# I2C_sensors.net
KiCad netlist of a schematic drawn in Altium Designer
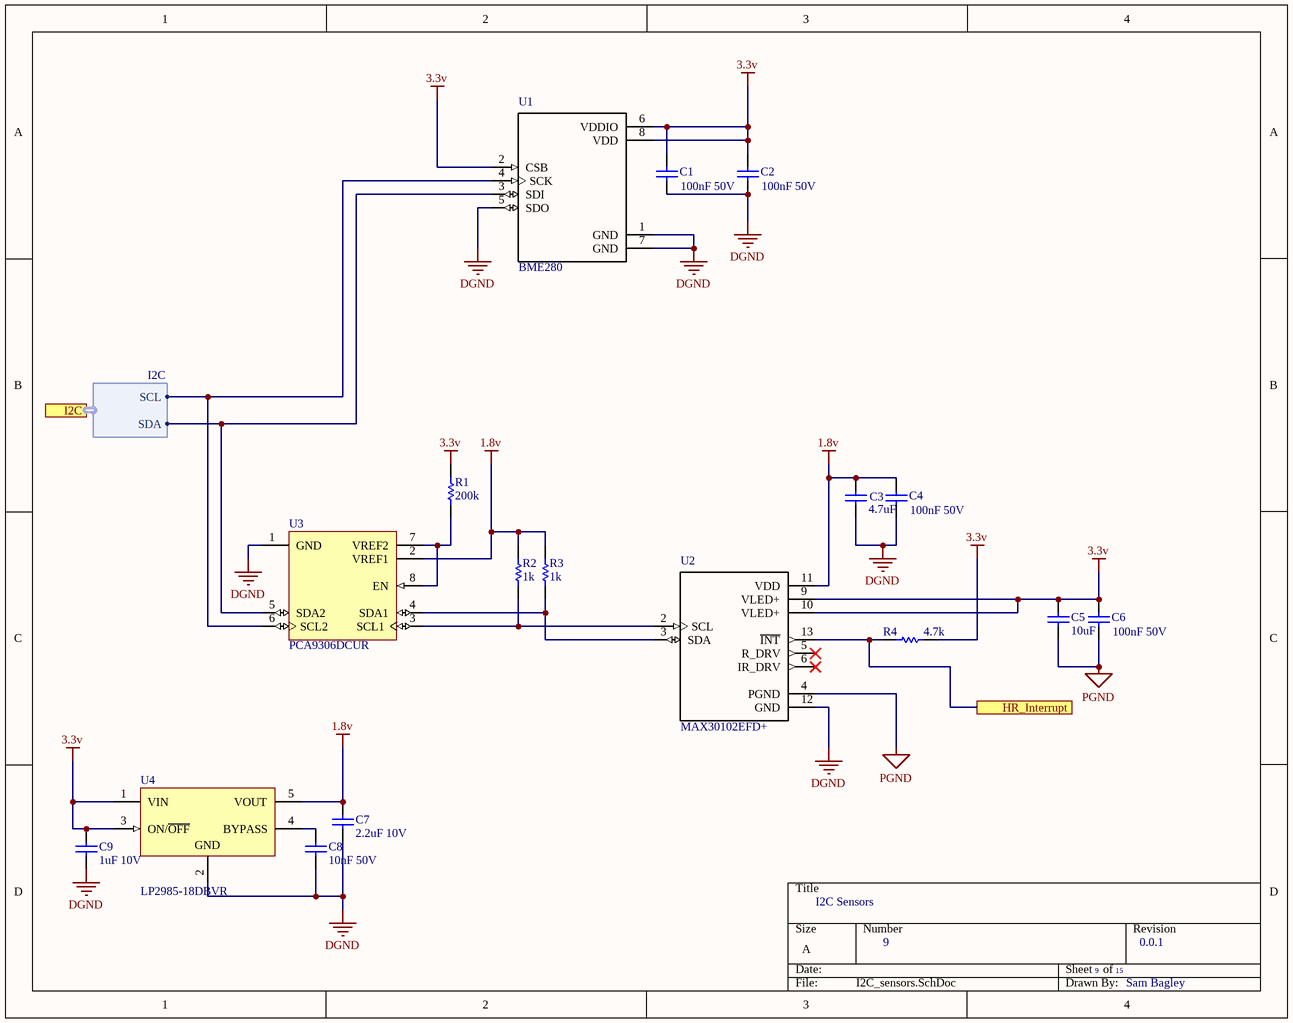
[diagram p0: I2C_sensors.SchDoc]

(export (version "E")
  (design (tool "Eeschema 10.0.6"))
  (components
    (comp (ref "C1")
      (value "100nF 50V")
      (footprint "CAPC0603(1608)100_M")
      (description "CAP 100nF 50V -20% to +80% 0603 (1608 Metric) Thickness 1mm SMD")
      (fields (field (name "TOLERANCE") "-20% to +80%"))
      (libsource (lib "Altium Content Vault") (part "CAP"))
    )
    (comp (ref "C2")
      (value "100nF 50V")
      (footprint "CAPC0603(1608)100_M")
      (description "CAP 100nF 50V -20% to +80% 0603 (1608 Metric) Thickness 1mm SMD")
      (fields (field (name "TOLERANCE") "-20% to +80%"))
      (libsource (lib "Altium Content Vault") (part "CAP"))
    )
    (comp (ref "C3")
      (value "4.7uF")
      (footprint "CAPC1608X87X35NL15T15")
      (description "CAP 4.7uF 0603")
      (fields (field (name "PART NUMBER") "C0603C475K8PACTU") (field (name "MANUFACTURER") "Kemet"))
      (libsource (lib "Altium Content Vault") (part "CAP"))
    )
    (comp (ref "C4")
      (value "100nF 50V")
      (footprint "CAPC0603(1608)100_M")
      (description "CAP 100nF 50V -20% to +80% 0603 (1608 Metric) Thickness 1mm SMD")
      (fields (field (name "TOLERANCE") "-20% to +80%"))
      (libsource (lib "Altium Content Vault") (part "CAP"))
    )
    (comp (ref "C5")
      (value "10uF")
      (footprint "CAPC1608X90X20LL10")
      (description "Chip Capacitor, 10 uF, +/- 10%, 10 V, -55 to 85 degC, 0603 (1608 Metric), RoHS, Tape and Reel")
      (fields
        (field (name "PCN PART NUMBER") "MLCCPartNumberChange30/Nov/2012")
        (field (name "TOLERANCE") "±10%")
      )
      (libsource (lib "Passives") (part "CMP-2000-04979-1"))
    )
    (comp (ref "C6")
      (value "100nF 50V")
      (footprint "CAPC0603(1608)100_M")
      (description "CAP 100nF 50V -20% to +80% 0603 (1608 Metric) Thickness 1mm SMD")
      (fields (field (name "TOLERANCE") "-20% to +80%"))
      (libsource (lib "Altium Content Vault") (part "CAP"))
    )
    (comp (ref "C7")
      (value "2.2uF 10V")
      (footprint "CAPC1608X90X35ML10T15")
      (description "CAP CER 2.2uF 10V 0603")
      (fields (field (name "MANUFACTURER") "Murata") (field (name "PART NUMBER") "GRM188R71A225KE15D"))
      (libsource (lib "Altium Content Vault") (part "CAP"))
    )
    (comp (ref "C8")
      (value "10nF 50V")
      (footprint "CAPC1608X90X40ML10T20")
      (description "Chip Capacitor, 10 nF, +/- 10%, 50 V, -55 to 125 degC, 0603 (1608 Metric), RoHS, Tape and Reel")
      (fields (field (name "MANUFACTURER") "Yageo") (field (name "TOLERANCE") "10%"))
      (libsource (lib "Altium Content Vault") (part "CAP-NP-2"))
    )
    (comp (ref "C9")
      (value "1uF 10V")
      (footprint "CAPC1608X90X35ML15T15")
      (description "CAP CER 1uF 10V 0603")
      (fields (field (name "MANUFACTURER") "Kemet") (field (name "PART NUMBER") "C0603C105K8PAC7867"))
      (libsource (lib "Altium Content Vault") (part "CAP"))
    )
    (comp (ref "R1")
      (value "200k")
      (footprint "RESC1608X55X30LL15T15")
      (fields (field (name "PART NUMBER") "ERJ-3GEYJ204V") (field (name "MANUFACTURER") "Panasonic"))
      (libsource (lib "Altium Content Vault") (part "RES"))
    )
    (comp (ref "R2")
      (value "1k")
      (footprint "RESC1608X55X30LL20T20")
      (fields (field (name "MANUFACTURER") "Panasonic") (field (name "PART NUMBER") "ERA3AEB102V"))
      (libsource (lib "Altium Content Vault") (part "RES"))
    )
    (comp (ref "R3")
      (value "1k")
      (footprint "RESC1608X55X30LL20T20")
      (fields (field (name "MANUFACTURER") "Panasonic") (field (name "PART NUMBER") "ERA3AEB102V"))
      (libsource (lib "Altium Content Vault") (part "RES"))
    )
    (comp (ref "R4")
      (value "4.7k")
      (footprint "RESC1608X55X30LL15T15")
      (fields (field (name "PART NUMBER") "ERJ3EKF4701V") (field (name "MANUFACTURER") "Panasonic"))
      (libsource (lib "Altium Content Vault") (part "RES"))
    )
    (comp (ref "U1")
      (value "BME280")
      (footprint "*PSON65P250X250X100-8N")
      (description "Humidity Temperature Sensor 0 ~ 100% RH IÂ²C, SPI Â±3% 1s Surface Mount")
      (fields (field (name "MF") "Bosch"))
      (libsource (lib "Components") (part "BME280"))
    )
    (comp (ref "U2")
      (value "MAX30102EFD+")
      (footprint "MAX30201")
      (description "Oximeter/Heart Rate Sensor IÂ²C Output")
      (fields (field (name "MF") "Maxim Integrated"))
      (libsource (lib "Components") (part "MAX30102EFD+"))
    )
    (comp (ref "U3")
      (value "PCA9306DCUR")
      (footprint "DCU0008A_M")
      (fields (field (name "MANUFACTURER") "Texas Instruments"))
      (libsource (lib "Altium Content Vault") (part "TI-PCA9306-US8_DCU-8"))
    )
    (comp (ref "U4")
      (value "LP2985-18DBVR")
      (footprint "DBV0005A_M")
      (fields (field (name "MANUFACTURER") "Texas Instruments"))
      (libsource (lib "Altium Content Vault") (part "TI-LP2985_A-10DBV5"))
    )
  )
  (nets
    (net (code "2") (name "/HR_Interrupt") (class "Default")
      (node (ref "R4") (pin "1") (pinfunction "1_1") (pintype "passive"))
      (node (ref "U2") (pin "13") (pinfunction "~{INT}_13") (pintype "output"))
    )
    (net (code "4") (name "1.8v") (class "Default")
      (node (ref "C3") (pin "2") (pinfunction "2_2") (pintype "passive"))
      (node (ref "C4") (pin "2") (pinfunction "2_2") (pintype "passive"))
      (node (ref "C7") (pin "2") (pinfunction "2_2") (pintype "passive"))
      (node (ref "R2") (pin "2") (pinfunction "2_2") (pintype "passive"))
      (node (ref "R3") (pin "2") (pinfunction "2_2") (pintype "passive"))
      (node (ref "U2") (pin "11") (pinfunction "VDD_11") (pintype "power_in"))
      (node (ref "U3") (pin "2") (pinfunction "VREF1_2") (pintype "power_in"))
      (node (ref "U4") (pin "5") (pinfunction "VOUT_5") (pintype "power_in"))
    )
    (net (code "5") (name "3.3v") (class "Default")
      (node (ref "C1") (pin "2") (pinfunction "2_2") (pintype "passive"))
      (node (ref "C2") (pin "2") (pinfunction "2_2") (pintype "passive"))
      (node (ref "C5") (pin "2") (pinfunction "2_2") (pintype "passive"))
      (node (ref "C6") (pin "2") (pinfunction "2_2") (pintype "passive"))
      (node (ref "C9") (pin "2") (pinfunction "2_2") (pintype "passive"))
      (node (ref "R1") (pin "2") (pinfunction "2_2") (pintype "passive"))
      (node (ref "R4") (pin "2") (pinfunction "2_2") (pintype "passive"))
      (node (ref "U1") (pin "2") (pinfunction "CSB_2") (pintype "input"))
      (node (ref "U1") (pin "6") (pinfunction "VDDIO_6") (pintype "power_in"))
      (node (ref "U1") (pin "8") (pinfunction "VDD_8") (pintype "power_in"))
      (node (ref "U2") (pin "10") (pinfunction "VLED+_10") (pintype "power_in"))
      (node (ref "U2") (pin "9") (pinfunction "VLED+_9") (pintype "power_in"))
      (node (ref "U4") (pin "1") (pinfunction "VIN_1") (pintype "power_in"))
      (node (ref "U4") (pin "3") (pinfunction "ON/~{OFF}_3") (pintype "input"))
    )
    (net (code "6") (name "DGND") (class "Default")
      (node (ref "C1") (pin "1") (pinfunction "1_1") (pintype "passive"))
      (node (ref "C2") (pin "1") (pinfunction "1_1") (pintype "passive"))
      (node (ref "C3") (pin "1") (pinfunction "1_1") (pintype "passive"))
      (node (ref "C4") (pin "1") (pinfunction "1_1") (pintype "passive"))
      (node (ref "C7") (pin "1") (pinfunction "1_1") (pintype "passive"))
      (node (ref "C8") (pin "1") (pinfunction "1_1") (pintype "passive"))
      (node (ref "C9") (pin "1") (pinfunction "1_1") (pintype "passive"))
      (node (ref "U1") (pin "1") (pinfunction "GND_1") (pintype "power_in"))
      (node (ref "U1") (pin "5") (pinfunction "SDO_5") (pintype "bidirectional"))
      (node (ref "U1") (pin "7") (pinfunction "GND_7") (pintype "power_in"))
      (node (ref "U2") (pin "12") (pinfunction "GND_12") (pintype "power_in"))
      (node (ref "U3") (pin "1") (pinfunction "GND_1") (pintype "power_in"))
      (node (ref "U4") (pin "2") (pinfunction "GND_2") (pintype "power_in"))
    )
    (net (code "7") (name "Net-(U1-SCK)") (class "Default")
      (node (ref "U1") (pin "4") (pinfunction "SCK_4") (pintype "input"))
      (node (ref "U3") (pin "6") (pinfunction "SCL2_6") (pintype "bidirectional"))
    )
    (net (code "8") (name "Net-(U1-SDI)") (class "Default")
      (node (ref "U1") (pin "3") (pinfunction "SDI_3") (pintype "bidirectional"))
      (node (ref "U3") (pin "5") (pinfunction "SDA2_5") (pintype "bidirectional"))
    )
    (net (code "9") (name "Net-(U2-SCL)") (class "Default")
      (node (ref "R2") (pin "1") (pinfunction "1_1") (pintype "passive"))
      (node (ref "U2") (pin "2") (pinfunction "SCL_2") (pintype "input"))
      (node (ref "U3") (pin "3") (pinfunction "SCL1_3") (pintype "bidirectional"))
    )
    (net (code "10") (name "Net-(U2-SDA)") (class "Default")
      (node (ref "R3") (pin "1") (pinfunction "1_1") (pintype "passive"))
      (node (ref "U2") (pin "3") (pinfunction "SDA_3") (pintype "bidirectional"))
      (node (ref "U3") (pin "4") (pinfunction "SDA1_4") (pintype "bidirectional"))
    )
    (net (code "11") (name "Net-(U3-EN)") (class "Default")
      (node (ref "R1") (pin "1") (pinfunction "1_1") (pintype "passive"))
      (node (ref "U3") (pin "7") (pinfunction "VREF2_7") (pintype "power_in"))
      (node (ref "U3") (pin "8") (pinfunction "EN_8") (pintype "input"))
    )
    (net (code "12") (name "Net-(U4-BYPASS)") (class "Default")
      (node (ref "C8") (pin "2") (pinfunction "2_2") (pintype "passive"))
      (node (ref "U4") (pin "4") (pinfunction "BYPASS_4") (pintype "passive"))
    )
    (net (code "13") (name "PGND") (class "Default")
      (node (ref "C5") (pin "1") (pinfunction "1_1") (pintype "passive"))
      (node (ref "C6") (pin "1") (pinfunction "1_1") (pintype "passive"))
      (node (ref "U2") (pin "4") (pinfunction "PGND_4") (pintype "power_in"))
    )
    (net (code "14") (name "unconnected-(U2-IR_DRV-Pad6)") (class "Default")
      (node (ref "U2") (pin "6") (pinfunction "IR_DRV_6") (pintype "output+no_connect"))
    )
    (net (code "15") (name "unconnected-(U2-R_DRV-Pad5)") (class "Default")
      (node (ref "U2") (pin "5") (pinfunction "R_DRV_5") (pintype "output+no_connect"))
    )
  )
)
